# mt2_redraw.net
KiCad netlist of a schematic drawn in EAGLE
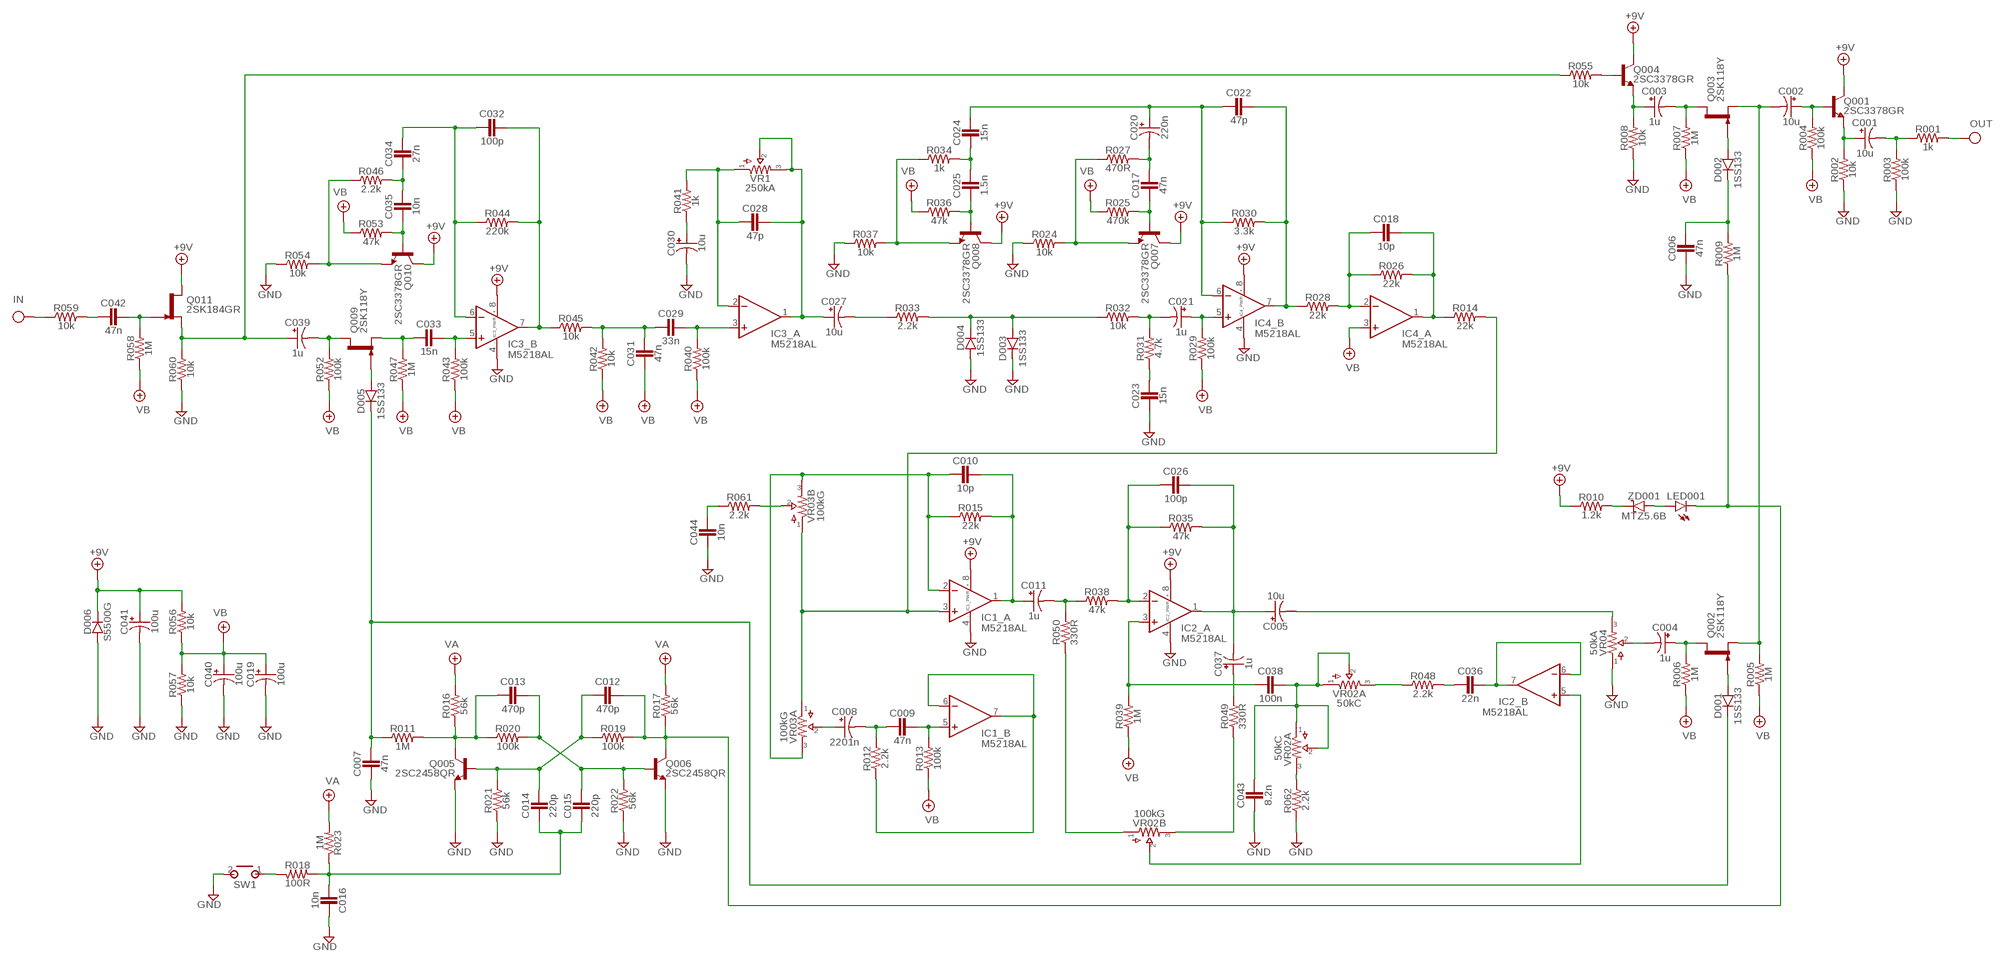
[diagram p0: schematic, sheet 1]

(export (version "E")
  (design (tool "Eeschema 10.0.6"))
  (components
    (comp (ref "C001")
      (value "10u")
      (footprint "eagle-import:050_020")
      (libsource (lib "eagle-import") (part "0500"))
    )
    (comp (ref "C002")
      (value "10u")
      (footprint "eagle-import:050_020")
      (libsource (lib "eagle-import") (part "0500"))
    )
    (comp (ref "C003")
      (value "1u")
      (footprint "eagle-import:050_020")
      (libsource (lib "eagle-import") (part "0500"))
    )
    (comp (ref "C004")
      (value "1u")
      (footprint "eagle-import:050_020")
      (libsource (lib "eagle-import") (part "0500"))
    )
    (comp (ref "C005")
      (value "10u")
      (footprint "eagle-import:050_020")
      (libsource (lib "eagle-import") (part "0500"))
    )
    (comp (ref "C006")
      (value "47n")
      (footprint "eagle-import:BOX_SMALL")
      (libsource (lib "eagle-import") (part "CER/FILMBOX.1"))
    )
    (comp (ref "C007")
      (value "47n")
      (footprint "eagle-import:BOX_SMALL")
      (libsource (lib "eagle-import") (part "CER/FILMBOX.1"))
    )
    (comp (ref "C008")
      (value "2201n")
      (footprint "eagle-import:050_020")
      (libsource (lib "eagle-import") (part "0500"))
    )
    (comp (ref "C009")
      (value "47n")
      (footprint "eagle-import:BOX_SMALL")
      (libsource (lib "eagle-import") (part "CER/FILMBOX.1"))
    )
    (comp (ref "C010")
      (value "10p")
      (footprint "eagle-import:BOX_SMALL")
      (libsource (lib "eagle-import") (part "CER/FILMBOX.1"))
    )
    (comp (ref "C011")
      (value "1u")
      (footprint "eagle-import:050_020")
      (libsource (lib "eagle-import") (part "0500"))
    )
    (comp (ref "C012")
      (value "470p")
      (footprint "eagle-import:BOX_SMALL")
      (libsource (lib "eagle-import") (part "CER/FILMBOX.1"))
    )
    (comp (ref "C013")
      (value "470p")
      (footprint "eagle-import:BOX_SMALL")
      (libsource (lib "eagle-import") (part "CER/FILMBOX.1"))
    )
    (comp (ref "C014")
      (value "220p")
      (footprint "eagle-import:BOX_SMALL")
      (libsource (lib "eagle-import") (part "CER/FILMBOX.1"))
    )
    (comp (ref "C015")
      (value "220p")
      (footprint "eagle-import:BOX_SMALL")
      (libsource (lib "eagle-import") (part "CER/FILMBOX.1"))
    )
    (comp (ref "C016")
      (value "10n")
      (footprint "eagle-import:BOX_SMALL")
      (libsource (lib "eagle-import") (part "CER/FILMBOX.1"))
    )
    (comp (ref "C017")
      (value "47n")
      (footprint "eagle-import:BOX_SMALL")
      (libsource (lib "eagle-import") (part "CER/FILMBOX.1"))
    )
    (comp (ref "C018")
      (value "10p")
      (footprint "eagle-import:BOX_SMALL")
      (libsource (lib "eagle-import") (part "CER/FILMBOX.1"))
    )
    (comp (ref "C019")
      (value "100u")
      (footprint "eagle-import:050_020")
      (libsource (lib "eagle-import") (part "0500"))
    )
    (comp (ref "C020")
      (value "220n")
      (footprint "eagle-import:050_020")
      (libsource (lib "eagle-import") (part "0500"))
    )
    (comp (ref "C021")
      (value "1u")
      (footprint "eagle-import:050_020")
      (libsource (lib "eagle-import") (part "0500"))
    )
    (comp (ref "C022")
      (value "47p")
      (footprint "eagle-import:BOX_SMALL")
      (libsource (lib "eagle-import") (part "CER/FILMBOX.1"))
    )
    (comp (ref "C023")
      (value "15n")
      (footprint "eagle-import:BOX_SMALL")
      (libsource (lib "eagle-import") (part "CER/FILMBOX.1"))
    )
    (comp (ref "C024")
      (value "15n")
      (footprint "eagle-import:BOX_SMALL")
      (libsource (lib "eagle-import") (part "CER/FILMBOX.1"))
    )
    (comp (ref "C025")
      (value "1.5n")
      (footprint "eagle-import:BOX_SMALL")
      (libsource (lib "eagle-import") (part "CER/FILMBOX.1"))
    )
    (comp (ref "C026")
      (value "100p")
      (footprint "eagle-import:BOX_SMALL")
      (libsource (lib "eagle-import") (part "CER/FILMBOX.1"))
    )
    (comp (ref "C027")
      (value "10u")
      (footprint "eagle-import:050_020")
      (libsource (lib "eagle-import") (part "0500"))
    )
    (comp (ref "C028")
      (value "47p")
      (footprint "eagle-import:BOX_SMALL")
      (libsource (lib "eagle-import") (part "CER/FILMBOX.1"))
    )
    (comp (ref "C029")
      (value "33n")
      (footprint "eagle-import:BOX_SMALL")
      (libsource (lib "eagle-import") (part "CER/FILMBOX.1"))
    )
    (comp (ref "C030")
      (value "10u")
      (footprint "eagle-import:050_020")
      (libsource (lib "eagle-import") (part "0500"))
    )
    (comp (ref "C031")
      (value "47n")
      (footprint "eagle-import:BOX_SMALL")
      (libsource (lib "eagle-import") (part "CER/FILMBOX.1"))
    )
    (comp (ref "C032")
      (value "100p")
      (footprint "eagle-import:BOX_SMALL")
      (libsource (lib "eagle-import") (part "CER/FILMBOX.1"))
    )
    (comp (ref "C033")
      (value "15n")
      (footprint "eagle-import:BOX_SMALL")
      (libsource (lib "eagle-import") (part "CER/FILMBOX.1"))
    )
    (comp (ref "C034")
      (value "27n")
      (footprint "eagle-import:BOX_SMALL")
      (libsource (lib "eagle-import") (part "CER/FILMBOX.1"))
    )
    (comp (ref "C035")
      (value "10n")
      (footprint "eagle-import:BOX_SMALL")
      (libsource (lib "eagle-import") (part "CER/FILMBOX.1"))
    )
    (comp (ref "C036")
      (value "22n")
      (footprint "eagle-import:BOX_SMALL")
      (libsource (lib "eagle-import") (part "CER/FILMBOX.1"))
    )
    (comp (ref "C037")
      (value "1u")
      (footprint "eagle-import:050_020")
      (libsource (lib "eagle-import") (part "0500"))
    )
    (comp (ref "C038")
      (value "100n")
      (footprint "eagle-import:BOX_SMALL")
      (libsource (lib "eagle-import") (part "CER/FILMBOX.1"))
    )
    (comp (ref "C039")
      (value "1u")
      (footprint "eagle-import:050_020")
      (libsource (lib "eagle-import") (part "0500"))
    )
    (comp (ref "C040")
      (value "100u")
      (footprint "eagle-import:050_020")
      (libsource (lib "eagle-import") (part "0500"))
    )
    (comp (ref "C041")
      (value "100u")
      (footprint "eagle-import:050_020")
      (libsource (lib "eagle-import") (part "0500"))
    )
    (comp (ref "C042")
      (value "47n")
      (footprint "eagle-import:BOX_SMALL")
      (libsource (lib "eagle-import") (part "CER/FILMBOX.1"))
    )
    (comp (ref "C043")
      (value "8.2n")
      (footprint "eagle-import:BOX_SMALL")
      (libsource (lib "eagle-import") (part "CER/FILMBOX.1"))
    )
    (comp (ref "C044")
      (value "10n")
      (footprint "eagle-import:BOX_SMALL")
      (libsource (lib "eagle-import") (part "CER/FILMBOX.1"))
    )
    (comp (ref "D001")
      (value "1SS133")
      (footprint "eagle-import:DO35-2")
      (libsource (lib "eagle-import") (part "DO35.2"))
    )
    (comp (ref "D002")
      (value "1SS133")
      (footprint "eagle-import:DO35-2")
      (libsource (lib "eagle-import") (part "DO35.2"))
    )
    (comp (ref "D003")
      (value "1SS133")
      (footprint "eagle-import:DO35-2")
      (libsource (lib "eagle-import") (part "DO35.2"))
    )
    (comp (ref "D004")
      (value "1SS133")
      (footprint "eagle-import:DO35-2")
      (libsource (lib "eagle-import") (part "DO35.2"))
    )
    (comp (ref "D005")
      (value "1SS133")
      (footprint "eagle-import:DO35-2")
      (libsource (lib "eagle-import") (part "DO35.2"))
    )
    (comp (ref "D006")
      (value "S5500G")
      (footprint "eagle-import:DO35-2")
      (libsource (lib "eagle-import") (part "DO35.2"))
    )
    (comp (ref "IC1")
      (value "M5218AL")
      (footprint "eagle-import:DIL0")
      (libsource (lib "eagle-import") (part "DUALTH"))
    )
    (comp (ref "IC2")
      (value "M5218AL")
      (footprint "eagle-import:DIL0")
      (libsource (lib "eagle-import") (part "DUALTH"))
    )
    (comp (ref "IC3")
      (value "M5218AL")
      (footprint "eagle-import:DIL0")
      (libsource (lib "eagle-import") (part "DUALTH"))
    )
    (comp (ref "IC4")
      (value "M5218AL")
      (footprint "eagle-import:DIL0")
      (libsource (lib "eagle-import") (part "DUALTH"))
    )
    (comp (ref "LED001")
      (value "LED")
      (footprint "eagle-import:3MM_D")
      (libsource (lib "eagle-import") (part "LED"))
    )
    (comp (ref "Q001")
      (value "2SC3378GR")
      (footprint "eagle-import:TO92-")
      (libsource (lib "eagle-import") (part "2N3904"))
    )
    (comp (ref "Q002")
      (value "2SK118Y")
      (footprint "eagle-import:TO92-")
      (libsource (lib "eagle-import") (part "2N5457"))
    )
    (comp (ref "Q003")
      (value "2SK118Y")
      (footprint "eagle-import:TO92-")
      (libsource (lib "eagle-import") (part "2N5457"))
    )
    (comp (ref "Q004")
      (value "2SC3378GR")
      (footprint "eagle-import:TO92-")
      (libsource (lib "eagle-import") (part "2N3904"))
    )
    (comp (ref "Q005")
      (value "2SC2458QR")
      (footprint "eagle-import:TO92-")
      (libsource (lib "eagle-import") (part "2SC828A"))
    )
    (comp (ref "Q006")
      (value "2SC2458QR")
      (footprint "eagle-import:TO92-")
      (libsource (lib "eagle-import") (part "2SC828A"))
    )
    (comp (ref "Q007")
      (value "2SC3378GR")
      (footprint "eagle-import:TO92-")
      (libsource (lib "eagle-import") (part "2N3904"))
    )
    (comp (ref "Q008")
      (value "2SC3378GR")
      (footprint "eagle-import:TO92-")
      (libsource (lib "eagle-import") (part "2N3904"))
    )
    (comp (ref "Q009")
      (value "2SK118Y")
      (footprint "eagle-import:TO92-")
      (libsource (lib "eagle-import") (part "2N5457"))
    )
    (comp (ref "Q010")
      (value "2SC3378GR")
      (footprint "eagle-import:TO92-")
      (libsource (lib "eagle-import") (part "2N3904"))
    )
    (comp (ref "Q011")
      (value "2SK184GR")
      (footprint "eagle-import:TO92-")
      (libsource (lib "eagle-import") (part "2N5457"))
    )
    (comp (ref "R001")
      (value "1k")
      (footprint "eagle-import:R0207_3")
      (libsource (lib "eagle-import") (part "R_.3B"))
    )
    (comp (ref "R002")
      (value "10k")
      (footprint "eagle-import:R0207_3")
      (libsource (lib "eagle-import") (part "R_.3B"))
    )
    (comp (ref "R003")
      (value "100k")
      (footprint "eagle-import:R0207_3")
      (libsource (lib "eagle-import") (part "R_.3B"))
    )
    (comp (ref "R004")
      (value "100k")
      (footprint "eagle-import:R0207_3")
      (libsource (lib "eagle-import") (part "R_.3B"))
    )
    (comp (ref "R005")
      (value "1M")
      (footprint "eagle-import:R0207_3")
      (libsource (lib "eagle-import") (part "R_.3B"))
    )
    (comp (ref "R006")
      (value "1M")
      (footprint "eagle-import:R0207_3")
      (libsource (lib "eagle-import") (part "R_.3B"))
    )
    (comp (ref "R007")
      (value "1M")
      (footprint "eagle-import:R0207_3")
      (libsource (lib "eagle-import") (part "R_.3B"))
    )
    (comp (ref "R008")
      (value "10k")
      (footprint "eagle-import:R0207_3")
      (libsource (lib "eagle-import") (part "R_.3B"))
    )
    (comp (ref "R009")
      (value "1M")
      (footprint "eagle-import:R0207_3")
      (libsource (lib "eagle-import") (part "R_.3B"))
    )
    (comp (ref "R010")
      (value "1.2k")
      (footprint "eagle-import:R0207_3")
      (libsource (lib "eagle-import") (part "R_.3B"))
    )
    (comp (ref "R011")
      (value "1M")
      (footprint "eagle-import:R0207_3")
      (libsource (lib "eagle-import") (part "R_.3B"))
    )
    (comp (ref "R012")
      (value "2.2k")
      (footprint "eagle-import:R0207_3")
      (libsource (lib "eagle-import") (part "R_.3B"))
    )
    (comp (ref "R013")
      (value "100k")
      (footprint "eagle-import:R0207_3")
      (libsource (lib "eagle-import") (part "R_.3B"))
    )
    (comp (ref "R014")
      (value "22k")
      (footprint "eagle-import:R0207_3")
      (libsource (lib "eagle-import") (part "R_.3B"))
    )
    (comp (ref "R015")
      (value "22k")
      (footprint "eagle-import:R0207_3")
      (libsource (lib "eagle-import") (part "R_.3B"))
    )
    (comp (ref "R016")
      (value "56k")
      (footprint "eagle-import:R0207_3")
      (libsource (lib "eagle-import") (part "R_.3B"))
    )
    (comp (ref "R017")
      (value "56k")
      (footprint "eagle-import:R0207_3")
      (libsource (lib "eagle-import") (part "R_.3B"))
    )
    (comp (ref "R018")
      (value "100R")
      (footprint "eagle-import:R0207_3")
      (libsource (lib "eagle-import") (part "R_.3B"))
    )
    (comp (ref "R019")
      (value "100k")
      (footprint "eagle-import:R0207_3")
      (libsource (lib "eagle-import") (part "R_.3B"))
    )
    (comp (ref "R020")
      (value "100k")
      (footprint "eagle-import:R0207_3")
      (libsource (lib "eagle-import") (part "R_.3B"))
    )
    (comp (ref "R021")
      (value "56k")
      (footprint "eagle-import:R0207_3")
      (libsource (lib "eagle-import") (part "R_.3B"))
    )
    (comp (ref "R022")
      (value "56k")
      (footprint "eagle-import:R0207_3")
      (libsource (lib "eagle-import") (part "R_.3B"))
    )
    (comp (ref "R023")
      (value "1M")
      (footprint "eagle-import:R0207_3")
      (libsource (lib "eagle-import") (part "R_.3B"))
    )
    (comp (ref "R024")
      (value "10k")
      (footprint "eagle-import:R0207_3")
      (libsource (lib "eagle-import") (part "R_.3B"))
    )
    (comp (ref "R025")
      (value "470k")
      (footprint "eagle-import:R0207_3")
      (libsource (lib "eagle-import") (part "R_.3B"))
    )
    (comp (ref "R026")
      (value "22k")
      (footprint "eagle-import:R0207_3")
      (libsource (lib "eagle-import") (part "R_.3B"))
    )
    (comp (ref "R027")
      (value "470R")
      (footprint "eagle-import:R0207_3")
      (libsource (lib "eagle-import") (part "R_.3B"))
    )
    (comp (ref "R028")
      (value "22k")
      (footprint "eagle-import:R0207_3")
      (libsource (lib "eagle-import") (part "R_.3B"))
    )
    (comp (ref "R029")
      (value "100k")
      (footprint "eagle-import:R0207_3")
      (libsource (lib "eagle-import") (part "R_.3B"))
    )
    (comp (ref "R030")
      (value "3.3k")
      (footprint "eagle-import:R0207_3")
      (libsource (lib "eagle-import") (part "R_.3B"))
    )
    (comp (ref "R031")
      (value "4.7k")
      (footprint "eagle-import:R0207_3")
      (libsource (lib "eagle-import") (part "R_.3B"))
    )
    (comp (ref "R032")
      (value "10k")
      (footprint "eagle-import:R0207_3")
      (libsource (lib "eagle-import") (part "R_.3B"))
    )
    (comp (ref "R033")
      (value "2.2k")
      (footprint "eagle-import:R0207_3")
      (libsource (lib "eagle-import") (part "R_.3B"))
    )
    (comp (ref "R034")
      (value "1k")
      (footprint "eagle-import:R0207_3")
      (libsource (lib "eagle-import") (part "R_.3B"))
    )
    (comp (ref "R035")
      (value "47k")
      (footprint "eagle-import:R0207_3")
      (libsource (lib "eagle-import") (part "R_.3B"))
    )
    (comp (ref "R036")
      (value "47k")
      (footprint "eagle-import:R0207_3")
      (libsource (lib "eagle-import") (part "R_.3B"))
    )
    (comp (ref "R037")
      (value "10k")
      (footprint "eagle-import:R0207_3")
      (libsource (lib "eagle-import") (part "R_.3B"))
    )
    (comp (ref "R038")
      (value "47k")
      (footprint "eagle-import:R0207_3")
      (libsource (lib "eagle-import") (part "R_.3B"))
    )
    (comp (ref "R039")
      (value "1M")
      (footprint "eagle-import:R0207_3")
      (libsource (lib "eagle-import") (part "R_.3B"))
    )
    (comp (ref "R040")
      (value "100k")
      (footprint "eagle-import:R0207_3")
      (libsource (lib "eagle-import") (part "R_.3B"))
    )
    (comp (ref "R041")
      (value "1k")
      (footprint "eagle-import:R0207_3")
      (libsource (lib "eagle-import") (part "R_.3B"))
    )
    (comp (ref "R042")
      (value "10k")
      (footprint "eagle-import:R0207_3")
      (libsource (lib "eagle-import") (part "R_.3B"))
    )
    (comp (ref "R043")
      (value "100k")
      (footprint "eagle-import:R0207_3")
      (libsource (lib "eagle-import") (part "R_.3B"))
    )
    (comp (ref "R044")
      (value "220k")
      (footprint "eagle-import:R0207_3")
      (libsource (lib "eagle-import") (part "R_.3B"))
    )
    (comp (ref "R045")
      (value "10k")
      (footprint "eagle-import:R0207_3")
      (libsource (lib "eagle-import") (part "R_.3B"))
    )
    (comp (ref "R046")
      (value "2.2k")
      (footprint "eagle-import:R0207_3")
      (libsource (lib "eagle-import") (part "R_.3B"))
    )
    (comp (ref "R047")
      (value "1M")
      (footprint "eagle-import:R0207_3")
      (libsource (lib "eagle-import") (part "R_.3B"))
    )
    (comp (ref "R048")
      (value "2.2k")
      (footprint "eagle-import:R0207_3")
      (libsource (lib "eagle-import") (part "R_.3B"))
    )
    (comp (ref "R049")
      (value "330R")
      (footprint "eagle-import:R0207_3")
      (libsource (lib "eagle-import") (part "R_.3B"))
    )
    (comp (ref "R050")
      (value "330R")
      (footprint "eagle-import:R0207_3")
      (libsource (lib "eagle-import") (part "R_.3B"))
    )
    (comp (ref "R052")
      (value "100k")
      (footprint "eagle-import:R0207_3")
      (libsource (lib "eagle-import") (part "R_.3B"))
    )
    (comp (ref "R053")
      (value "47k")
      (footprint "eagle-import:R0207_3")
      (libsource (lib "eagle-import") (part "R_.3B"))
    )
    (comp (ref "R054")
      (value "10k")
      (footprint "eagle-import:R0207_3")
      (libsource (lib "eagle-import") (part "R_.3B"))
    )
    (comp (ref "R055")
      (value "10k")
      (footprint "eagle-import:R0207_3")
      (libsource (lib "eagle-import") (part "R_.3B"))
    )
    (comp (ref "R056")
      (value "10k")
      (footprint "eagle-import:R0207_3")
      (libsource (lib "eagle-import") (part "R_.3B"))
    )
    (comp (ref "R057")
      (value "10k")
      (footprint "eagle-import:R0207_3")
      (libsource (lib "eagle-import") (part "R_.3B"))
    )
    (comp (ref "R058")
      (value "1M")
      (footprint "eagle-import:R0207_3")
      (libsource (lib "eagle-import") (part "R_.3B"))
    )
    (comp (ref "R059")
      (value "10k")
      (footprint "eagle-import:R0207_3")
      (libsource (lib "eagle-import") (part "R_.3B"))
    )
    (comp (ref "R060")
      (value "10k")
      (footprint "eagle-import:R0207_3")
      (libsource (lib "eagle-import") (part "R_.3B"))
    )
    (comp (ref "R061")
      (value "2.2k")
      (footprint "eagle-import:R0207_3")
      (libsource (lib "eagle-import") (part "R_.3B"))
    )
    (comp (ref "R062")
      (value "2.2k")
      (footprint "eagle-import:R0207_3")
      (libsource (lib "eagle-import") (part "R_.3B"))
    )
    (comp (ref "SW1")
      (value "MOMENTARY")
      (footprint "eagle-import:SPST")
      (libsource (lib "eagle-import") (part "MOMENTARY"))
    )
    (comp (ref "VR1")
      (value "250kA")
      (footprint "eagle-import:16MM")
      (libsource (lib "eagle-import") (part "POTS16MM"))
    )
    (comp (ref "VR02A")
      (value "50kC")
      (footprint "eagle-import:16MM")
      (libsource (lib "eagle-import") (part "POTS16MM"))
    )
    (comp (ref "VR02A ")
      (value "50kC")
      (footprint "eagle-import:16MM")
      (libsource (lib "eagle-import") (part "POTS16MM"))
    )
    (comp (ref "VR02B")
      (value "100kG")
      (footprint "eagle-import:16MM")
      (libsource (lib "eagle-import") (part "POTS16MM"))
    )
    (comp (ref "VR03A")
      (value "100kG")
      (footprint "eagle-import:16MM")
      (libsource (lib "eagle-import") (part "POTS16MM"))
    )
    (comp (ref "VR03B")
      (value "100kG")
      (footprint "eagle-import:16MM")
      (libsource (lib "eagle-import") (part "POTS16MM"))
    )
    (comp (ref "VR04")
      (value "50kA")
      (footprint "eagle-import:16MM")
      (libsource (lib "eagle-import") (part "POTS16MM"))
    )
    (comp (ref "ZD001")
      (value "MTZ5.6B")
      (footprint "eagle-import:DO41-2")
      (libsource (lib "eagle-import") (part "ZENER.2"))
    )
  )
  (nets
    (net (code "1") (name "+9V") (class "Default")
      (node (ref "C041") (pin "+") (pinfunction "+_+") (pintype "passive"))
      (node (ref "D006") (pin "C") (pinfunction "C_C") (pintype "passive"))
      (node (ref "IC1") (pin "8") (pinfunction "V+_8") (pintype "power_in"))
      (node (ref "IC2") (pin "8") (pinfunction "V+_8") (pintype "power_in"))
      (node (ref "IC3") (pin "8") (pinfunction "V+_8") (pintype "power_in"))
      (node (ref "IC4") (pin "8") (pinfunction "V+_8") (pintype "power_in"))
      (node (ref "Q001") (pin "1") (pinfunction "C_1") (pintype "passive"))
      (node (ref "Q004") (pin "1") (pinfunction "C_1") (pintype "passive"))
      (node (ref "Q007") (pin "1") (pinfunction "C_1") (pintype "passive"))
      (node (ref "Q008") (pin "1") (pinfunction "C_1") (pintype "passive"))
      (node (ref "Q010") (pin "1") (pinfunction "C_1") (pintype "passive"))
      (node (ref "Q011") (pin "3") (pinfunction "D_3") (pintype "passive"))
      (node (ref "R010") (pin "1") (pinfunction "1_1") (pintype "passive"))
      (node (ref "R056") (pin "2") (pinfunction "2_2") (pintype "passive"))
    )
    (net (code "2") (name "GND") (class "Default")
      (node (ref "C006") (pin "2") (pinfunction "2_2") (pintype "passive"))
      (node (ref "C007") (pin "2") (pinfunction "2_2") (pintype "passive"))
      (node (ref "C016") (pin "2") (pinfunction "2_2") (pintype "passive"))
      (node (ref "C019") (pin "-") (pinfunction "-_-") (pintype "passive"))
      (node (ref "C023") (pin "2") (pinfunction "2_2") (pintype "passive"))
      (node (ref "C030") (pin "-") (pinfunction "-_-") (pintype "passive"))
      (node (ref "C040") (pin "-") (pinfunction "-_-") (pintype "passive"))
      (node (ref "C041") (pin "-") (pinfunction "-_-") (pintype "passive"))
      (node (ref "C043") (pin "2") (pinfunction "2_2") (pintype "passive"))
      (node (ref "C044") (pin "2") (pinfunction "2_2") (pintype "passive"))
      (node (ref "D003") (pin "C") (pinfunction "C_C") (pintype "passive"))
      (node (ref "D004") (pin "A") (pinfunction "A_A") (pintype "passive"))
      (node (ref "D006") (pin "A") (pinfunction "A_A") (pintype "passive"))
      (node (ref "IC1") (pin "4") (pinfunction "V-_4") (pintype "power_in"))
      (node (ref "IC2") (pin "4") (pinfunction "V-_4") (pintype "power_in"))
      (node (ref "IC3") (pin "4") (pinfunction "V-_4") (pintype "power_in"))
      (node (ref "IC4") (pin "4") (pinfunction "V-_4") (pintype "power_in"))
      (node (ref "Q005") (pin "3") (pinfunction "E_3") (pintype "passive"))
      (node (ref "Q006") (pin "3") (pinfunction "E_3") (pintype "passive"))
      (node (ref "R002") (pin "1") (pinfunction "1_1") (pintype "passive"))
      (node (ref "R003") (pin "1") (pinfunction "1_1") (pintype "passive"))
      (node (ref "R008") (pin "1") (pinfunction "1_1") (pintype "passive"))
      (node (ref "R021") (pin "1") (pinfunction "1_1") (pintype "passive"))
      (node (ref "R022") (pin "1") (pinfunction "1_1") (pintype "passive"))
      (node (ref "R024") (pin "1") (pinfunction "1_1") (pintype "passive"))
      (node (ref "R037") (pin "1") (pinfunction "1_1") (pintype "passive"))
      (node (ref "R054") (pin "1") (pinfunction "1_1") (pintype "passive"))
      (node (ref "R057") (pin "1") (pinfunction "1_1") (pintype "passive"))
      (node (ref "R060") (pin "1") (pinfunction "1_1") (pintype "passive"))
      (node (ref "R062") (pin "1") (pinfunction "1_1") (pintype "passive"))
      (node (ref "SW1") (pin "2") (pinfunction "S_2") (pintype "passive"))
      (node (ref "VR04") (pin "1") (pinfunction "1_1") (pintype "passive"))
    )
    (net (code "3") (name "IN") (class "Default")
      (node (ref "R059") (pin "1") (pinfunction "1_1") (pintype "passive"))
    )
    (net (code "4") (name "Net-(C001-Pad-)") (class "Default")
      (node (ref "C001") (pin "-") (pinfunction "-_-") (pintype "passive"))
      (node (ref "R001") (pin "1") (pinfunction "1_1") (pintype "passive"))
      (node (ref "R003") (pin "2") (pinfunction "2_2") (pintype "passive"))
    )
    (net (code "5") (name "Net-(C004-Pad-)") (class "Default")
      (node (ref "C004") (pin "-") (pinfunction "-_-") (pintype "passive"))
      (node (ref "VR04") (pin "2") (pinfunction "2_2") (pintype "passive"))
    )
    (net (code "6") (name "Net-(C005-Pad-)") (class "Default")
      (node (ref "C005") (pin "-") (pinfunction "-_-") (pintype "passive"))
      (node (ref "VR04") (pin "3") (pinfunction "3_3") (pintype "passive"))
    )
    (net (code "7") (name "Net-(C006-Pad1)") (class "Default")
      (node (ref "C006") (pin "1") (pinfunction "1_1") (pintype "passive"))
      (node (ref "D002") (pin "C") (pinfunction "C_C") (pintype "passive"))
      (node (ref "R009") (pin "2") (pinfunction "2_2") (pintype "passive"))
    )
    (net (code "8") (name "Net-(C007-Pad1)") (class "Default")
      (node (ref "C007") (pin "1") (pinfunction "1_1") (pintype "passive"))
      (node (ref "D001") (pin "C") (pinfunction "C_C") (pintype "passive"))
      (node (ref "D005") (pin "C") (pinfunction "C_C") (pintype "passive"))
      (node (ref "R011") (pin "1") (pinfunction "1_1") (pintype "passive"))
    )
    (net (code "9") (name "Net-(C008-Pad+)") (class "Default")
      (node (ref "C008") (pin "+") (pinfunction "+_+") (pintype "passive"))
      (node (ref "VR03A") (pin "2") (pinfunction "2_2") (pintype "passive"))
    )
    (net (code "10") (name "Net-(C008-Pad-)") (class "Default")
      (node (ref "C008") (pin "-") (pinfunction "-_-") (pintype "passive"))
      (node (ref "C009") (pin "2") (pinfunction "2_2") (pintype "passive"))
      (node (ref "R012") (pin "2") (pinfunction "2_2") (pintype "passive"))
    )
    (net (code "11") (name "Net-(C011-Pad-)") (class "Default")
      (node (ref "C011") (pin "-") (pinfunction "-_-") (pintype "passive"))
      (node (ref "R038") (pin "1") (pinfunction "1_1") (pintype "passive"))
      (node (ref "R050") (pin "2") (pinfunction "2_2") (pintype "passive"))
    )
    (net (code "12") (name "Net-(C014-Pad2)") (class "Default")
      (node (ref "C014") (pin "2") (pinfunction "2_2") (pintype "passive"))
      (node (ref "C015") (pin "2") (pinfunction "2_2") (pintype "passive"))
      (node (ref "C016") (pin "1") (pinfunction "1_1") (pintype "passive"))
      (node (ref "R018") (pin "1") (pinfunction "1_1") (pintype "passive"))
      (node (ref "R023") (pin "1") (pinfunction "1_1") (pintype "passive"))
    )
    (net (code "13") (name "Net-(C017-Pad1)") (class "Default")
      (node (ref "C017") (pin "1") (pinfunction "1_1") (pintype "passive"))
      (node (ref "C020") (pin "-") (pinfunction "-_-") (pintype "passive"))
      (node (ref "R027") (pin "2") (pinfunction "2_2") (pintype "passive"))
    )
    (net (code "14") (name "Net-(C021-Pad-)") (class "Default")
      (node (ref "C021") (pin "-") (pinfunction "-_-") (pintype "passive"))
      (node (ref "R031") (pin "2") (pinfunction "2_2") (pintype "passive"))
      (node (ref "R032") (pin "2") (pinfunction "2_2") (pintype "passive"))
    )
    (net (code "15") (name "Net-(C023-Pad1)") (class "Default")
      (node (ref "C023") (pin "1") (pinfunction "1_1") (pintype "passive"))
      (node (ref "R031") (pin "1") (pinfunction "1_1") (pintype "passive"))
    )
    (net (code "16") (name "Net-(C024-Pad2)") (class "Default")
      (node (ref "C024") (pin "2") (pinfunction "2_2") (pintype "passive"))
      (node (ref "C025") (pin "1") (pinfunction "1_1") (pintype "passive"))
      (node (ref "R034") (pin "2") (pinfunction "2_2") (pintype "passive"))
    )
    (net (code "17") (name "Net-(C027-Pad-)") (class "Default")
      (node (ref "C027") (pin "-") (pinfunction "-_-") (pintype "passive"))
      (node (ref "R033") (pin "1") (pinfunction "1_1") (pintype "passive"))
    )
    (net (code "18") (name "Net-(C029-Pad2)") (class "Default")
      (node (ref "C029") (pin "2") (pinfunction "2_2") (pintype "passive"))
      (node (ref "C031") (pin "1") (pinfunction "1_1") (pintype "passive"))
      (node (ref "R042") (pin "2") (pinfunction "2_2") (pintype "passive"))
      (node (ref "R045") (pin "2") (pinfunction "2_2") (pintype "passive"))
    )
    (net (code "19") (name "Net-(C030-Pad+)") (class "Default")
      (node (ref "C030") (pin "+") (pinfunction "+_+") (pintype "passive"))
      (node (ref "R041") (pin "1") (pinfunction "1_1") (pintype "passive"))
    )
    (net (code "20") (name "Net-(C034-Pad2)") (class "Default")
      (node (ref "C034") (pin "2") (pinfunction "2_2") (pintype "passive"))
      (node (ref "C035") (pin "1") (pinfunction "1_1") (pintype "passive"))
      (node (ref "R046") (pin "2") (pinfunction "2_2") (pintype "passive"))
    )
    (net (code "21") (name "Net-(C036-Pad2)") (class "Default")
      (node (ref "C036") (pin "2") (pinfunction "2_2") (pintype "passive"))
      (node (ref "R048") (pin "2") (pinfunction "2_2") (pintype "passive"))
    )
    (net (code "22") (name "Net-(C037-Pad+)") (class "Default")
      (node (ref "C037") (pin "+") (pinfunction "+_+") (pintype "passive"))
      (node (ref "R049") (pin "2") (pinfunction "2_2") (pintype "passive"))
    )
    (net (code "23") (name "Net-(C038-Pad1)") (class "Default")
      (node (ref "C038") (pin "1") (pinfunction "1_1") (pintype "passive"))
      (node (ref "C043") (pin "1") (pinfunction "1_1") (pintype "passive"))
      (node (ref "VR02A") (pin "1") (pinfunction "1_1") (pintype "passive"))
      (node (ref "VR02A") (pin "2") (pinfunction "2_2") (pintype "passive"))
      (node (ref "VR02A ") (pin "1") (pinfunction "1_1") (pintype "passive"))
      (node (ref "VR02A ") (pin "2") (pinfunction "2_2") (pintype "passive"))
    )
    (net (code "24") (name "Net-(C042-Pad2)") (class "Default")
      (node (ref "C042") (pin "2") (pinfunction "2_2") (pintype "passive"))
      (node (ref "R059") (pin "2") (pinfunction "2_2") (pintype "passive"))
    )
    (net (code "25") (name "Net-(C044-Pad1)") (class "Default")
      (node (ref "C044") (pin "1") (pinfunction "1_1") (pintype "passive"))
      (node (ref "R061") (pin "1") (pinfunction "1_1") (pintype "passive"))
    )
    (net (code "26") (name "Net-(D003-PadA)") (class "Default")
      (node (ref "D003") (pin "A") (pinfunction "A_A") (pintype "passive"))
      (node (ref "D004") (pin "C") (pinfunction "C_C") (pintype "passive"))
      (node (ref "R032") (pin "1") (pinfunction "1_1") (pintype "passive"))
      (node (ref "R033") (pin "2") (pinfunction "2_2") (pintype "passive"))
    )
    (net (code "27") (name "Net-(IC1A-+IN)") (class "Default")
      (node (ref "IC1") (pin "3") (pinfunction "+IN_3") (pintype "input"))
      (node (ref "R014") (pin "2") (pinfunction "2_2") (pintype "passive"))
      (node (ref "VR03A") (pin "1") (pinfunction "1_1") (pintype "passive"))
      (node (ref "VR03B") (pin "1") (pinfunction "1_1") (pintype "passive"))
    )
    (net (code "28") (name "Net-(IC1A--IN)") (class "Default")
      (node (ref "C010") (pin "2") (pinfunction "2_2") (pintype "passive"))
      (node (ref "IC1") (pin "2") (pinfunction "-IN_2") (pintype "input"))
      (node (ref "R015") (pin "1") (pinfunction "1_1") (pintype "passive"))
      (node (ref "VR03A") (pin "3") (pinfunction "3_3") (pintype "passive"))
      (node (ref "VR03B") (pin "3") (pinfunction "3_3") (pintype "passive"))
    )
    (net (code "29") (name "Net-(IC1A-OUT)") (class "Default")
      (node (ref "C010") (pin "1") (pinfunction "1_1") (pintype "passive"))
      (node (ref "C011") (pin "+") (pinfunction "+_+") (pintype "passive"))
      (node (ref "IC1") (pin "1") (pinfunction "OUT_1") (pintype "output"))
      (node (ref "R015") (pin "2") (pinfunction "2_2") (pintype "passive"))
    )
    (net (code "30") (name "Net-(IC1B-+IN)") (class "Default")
      (node (ref "C009") (pin "1") (pinfunction "1_1") (pintype "passive"))
      (node (ref "IC1") (pin "5") (pinfunction "+IN_5") (pintype "input"))
      (node (ref "R013") (pin "2") (pinfunction "2_2") (pintype "passive"))
    )
    (net (code "31") (name "Net-(IC1B--IN)") (class "Default")
      (node (ref "IC1") (pin "6") (pinfunction "-IN_6") (pintype "input"))
      (node (ref "IC1") (pin "7") (pinfunction "OUT_7") (pintype "output"))
      (node (ref "R012") (pin "1") (pinfunction "1_1") (pintype "passive"))
    )
    (net (code "32") (name "Net-(IC2A-+IN)") (class "Default")
      (node (ref "C038") (pin "2") (pinfunction "2_2") (pintype "passive"))
      (node (ref "IC2") (pin "3") (pinfunction "+IN_3") (pintype "input"))
      (node (ref "R039") (pin "2") (pinfunction "2_2") (pintype "passive"))
    )
    (net (code "33") (name "Net-(IC2A--IN)") (class "Default")
      (node (ref "C026") (pin "2") (pinfunction "2_2") (pintype "passive"))
      (node (ref "IC2") (pin "2") (pinfunction "-IN_2") (pintype "input"))
      (node (ref "R035") (pin "1") (pinfunction "1_1") (pintype "passive"))
      (node (ref "R038") (pin "2") (pinfunction "2_2") (pintype "passive"))
    )
    (net (code "34") (name "Net-(IC2A-OUT)") (class "Default")
      (node (ref "C005") (pin "+") (pinfunction "+_+") (pintype "passive"))
      (node (ref "C026") (pin "1") (pinfunction "1_1") (pintype "passive"))
      (node (ref "C037") (pin "-") (pinfunction "-_-") (pintype "passive"))
      (node (ref "IC2") (pin "1") (pinfunction "OUT_1") (pintype "output"))
      (node (ref "R035") (pin "2") (pinfunction "2_2") (pintype "passive"))
    )
    (net (code "35") (name "Net-(IC2B-+IN)") (class "Default")
      (node (ref "IC2") (pin "5") (pinfunction "+IN_5") (pintype "input"))
      (node (ref "VR02B") (pin "2") (pinfunction "2_2") (pintype "passive"))
    )
    (net (code "36") (name "Net-(IC2B--IN)") (class "Default")
      (node (ref "C036") (pin "1") (pinfunction "1_1") (pintype "passive"))
      (node (ref "IC2") (pin "6") (pinfunction "-IN_6") (pintype "input"))
      (node (ref "IC2") (pin "7") (pinfunction "OUT_7") (pintype "output"))
    )
    (net (code "37") (name "Net-(IC3A-+IN)") (class "Default")
      (node (ref "C029") (pin "1") (pinfunction "1_1") (pintype "passive"))
      (node (ref "IC3") (pin "3") (pinfunction "+IN_3") (pintype "input"))
      (node (ref "R040") (pin "2") (pinfunction "2_2") (pintype "passive"))
    )
    (net (code "38") (name "Net-(IC3A--IN)") (class "Default")
      (node (ref "C028") (pin "2") (pinfunction "2_2") (pintype "passive"))
      (node (ref "IC3") (pin "2") (pinfunction "-IN_2") (pintype "input"))
      (node (ref "R041") (pin "2") (pinfunction "2_2") (pintype "passive"))
      (node (ref "VR1") (pin "1") (pinfunction "1_1") (pintype "passive"))
    )
    (net (code "39") (name "Net-(IC3A-OUT)") (class "Default")
      (node (ref "C027") (pin "+") (pinfunction "+_+") (pintype "passive"))
      (node (ref "C028") (pin "1") (pinfunction "1_1") (pintype "passive"))
      (node (ref "IC3") (pin "1") (pinfunction "OUT_1") (pintype "output"))
      (node (ref "VR1") (pin "2") (pinfunction "2_2") (pintype "passive"))
      (node (ref "VR1") (pin "3") (pinfunction "3_3") (pintype "passive"))
    )
    (net (code "40") (name "Net-(IC3B-+IN)") (class "Default")
      (node (ref "C033") (pin "1") (pinfunction "1_1") (pintype "passive"))
      (node (ref "IC3") (pin "5") (pinfunction "+IN_5") (pintype "input"))
      (node (ref "R043") (pin "2") (pinfunction "2_2") (pintype "passive"))
    )
    (net (code "41") (name "Net-(IC3B--IN)") (class "Default")
      (node (ref "C032") (pin "2") (pinfunction "2_2") (pintype "passive"))
      (node (ref "C034") (pin "1") (pinfunction "1_1") (pintype "passive"))
      (node (ref "IC3") (pin "6") (pinfunction "-IN_6") (pintype "input"))
      (node (ref "R044") (pin "1") (pinfunction "1_1") (pintype "passive"))
    )
    (net (code "42") (name "Net-(IC3B-OUT)") (class "Default")
      (node (ref "C032") (pin "1") (pinfunction "1_1") (pintype "passive"))
      (node (ref "IC3") (pin "7") (pinfunction "OUT_7") (pintype "output"))
      (node (ref "R044") (pin "2") (pinfunction "2_2") (pintype "passive"))
      (node (ref "R045") (pin "1") (pinfunction "1_1") (pintype "passive"))
    )
    (net (code "43") (name "Net-(IC4A--IN)") (class "Default")
      (node (ref "C018") (pin "2") (pinfunction "2_2") (pintype "passive"))
      (node (ref "IC4") (pin "2") (pinfunction "-IN_2") (pintype "input"))
      (node (ref "R026") (pin "1") (pinfunction "1_1") (pintype "passive"))
      (node (ref "R028") (pin "2") (pinfunction "2_2") (pintype "passive"))
    )
    (net (code "44") (name "Net-(IC4A-OUT)") (class "Default")
      (node (ref "C018") (pin "1") (pinfunction "1_1") (pintype "passive"))
      (node (ref "IC4") (pin "1") (pinfunction "OUT_1") (pintype "output"))
      (node (ref "R014") (pin "1") (pinfunction "1_1") (pintype "passive"))
      (node (ref "R026") (pin "2") (pinfunction "2_2") (pintype "passive"))
    )
    (net (code "45") (name "Net-(IC4B-+IN)") (class "Default")
      (node (ref "C021") (pin "+") (pinfunction "+_+") (pintype "passive"))
      (node (ref "IC4") (pin "5") (pinfunction "+IN_5") (pintype "input"))
      (node (ref "R029") (pin "2") (pinfunction "2_2") (pintype "passive"))
    )
    (net (code "46") (name "Net-(IC4B--IN)") (class "Default")
      (node (ref "C020") (pin "+") (pinfunction "+_+") (pintype "passive"))
      (node (ref "C022") (pin "2") (pinfunction "2_2") (pintype "passive"))
      (node (ref "C024") (pin "1") (pinfunction "1_1") (pintype "passive"))
      (node (ref "IC4") (pin "6") (pinfunction "-IN_6") (pintype "input"))
      (node (ref "R030") (pin "1") (pinfunction "1_1") (pintype "passive"))
    )
    (net (code "47") (name "Net-(IC4B-OUT)") (class "Default")
      (node (ref "C022") (pin "1") (pinfunction "1_1") (pintype "passive"))
      (node (ref "IC4") (pin "7") (pinfunction "OUT_7") (pintype "output"))
      (node (ref "R028") (pin "1") (pinfunction "1_1") (pintype "passive"))
      (node (ref "R030") (pin "2") (pinfunction "2_2") (pintype "passive"))
    )
    (net (code "48") (name "Net-(LED001-A)") (class "Default")
      (node (ref "LED001") (pin "ANODE") (pinfunction "A_ANODE") (pintype "passive"))
      (node (ref "ZD001") (pin "A") (pinfunction "A_A") (pintype "passive"))
    )
    (net (code "49") (name "Net-(LED001-C)") (class "Default")
      (node (ref "C012") (pin "1") (pinfunction "1_1") (pintype "passive"))
      (node (ref "LED001") (pin "P$1") (pinfunction "C_P$1") (pintype "passive"))
      (node (ref "Q006") (pin "2") (pinfunction "C_2") (pintype "passive"))
      (node (ref "R009") (pin "1") (pinfunction "1_1") (pintype "passive"))
      (node (ref "R017") (pin "1") (pinfunction "1_1") (pintype "passive"))
      (node (ref "R019") (pin "2") (pinfunction "2_2") (pintype "passive"))
    )
    (net (code "50") (name "Net-(Q001-B)") (class "Default")
      (node (ref "C002") (pin "+") (pinfunction "+_+") (pintype "passive"))
      (node (ref "Q001") (pin "2") (pinfunction "B_2") (pintype "passive"))
      (node (ref "R004") (pin "2") (pinfunction "2_2") (pintype "passive"))
    )
    (net (code "51") (name "Net-(Q001-E)") (class "Default")
      (node (ref "C001") (pin "+") (pinfunction "+_+") (pintype "passive"))
      (node (ref "Q001") (pin "3") (pinfunction "E_3") (pintype "passive"))
      (node (ref "R002") (pin "2") (pinfunction "2_2") (pintype "passive"))
    )
    (net (code "52") (name "Net-(Q002-D)") (class "Default")
      (node (ref "C004") (pin "+") (pinfunction "+_+") (pintype "passive"))
      (node (ref "Q002") (pin "3") (pinfunction "D_3") (pintype "passive"))
      (node (ref "R006") (pin "2") (pinfunction "2_2") (pintype "passive"))
    )
    (net (code "53") (name "Net-(Q002-G)") (class "Default")
      (node (ref "D001") (pin "A") (pinfunction "A_A") (pintype "passive"))
      (node (ref "Q002") (pin "1") (pinfunction "G_1") (pintype "passive"))
    )
    (net (code "54") (name "Net-(Q002-S)") (class "Default")
      (node (ref "C002") (pin "-") (pinfunction "-_-") (pintype "passive"))
      (node (ref "Q002") (pin "2") (pinfunction "S_2") (pintype "passive"))
      (node (ref "Q003") (pin "2") (pinfunction "S_2") (pintype "passive"))
      (node (ref "R005") (pin "2") (pinfunction "2_2") (pintype "passive"))
    )
    (net (code "55") (name "Net-(Q003-D)") (class "Default")
      (node (ref "C003") (pin "-") (pinfunction "-_-") (pintype "passive"))
      (node (ref "Q003") (pin "3") (pinfunction "D_3") (pintype "passive"))
      (node (ref "R007") (pin "2") (pinfunction "2_2") (pintype "passive"))
    )
    (net (code "56") (name "Net-(Q003-G)") (class "Default")
      (node (ref "D002") (pin "A") (pinfunction "A_A") (pintype "passive"))
      (node (ref "Q003") (pin "1") (pinfunction "G_1") (pintype "passive"))
    )
    (net (code "57") (name "Net-(Q004-B)") (class "Default")
      (node (ref "Q004") (pin "2") (pinfunction "B_2") (pintype "passive"))
      (node (ref "R055") (pin "2") (pinfunction "2_2") (pintype "passive"))
    )
    (net (code "58") (name "Net-(Q004-E)") (class "Default")
      (node (ref "C003") (pin "+") (pinfunction "+_+") (pintype "passive"))
      (node (ref "Q004") (pin "3") (pinfunction "E_3") (pintype "passive"))
      (node (ref "R008") (pin "2") (pinfunction "2_2") (pintype "passive"))
    )
    (net (code "59") (name "Net-(Q005-B)") (class "Default")
      (node (ref "C012") (pin "2") (pinfunction "2_2") (pintype "passive"))
      (node (ref "C014") (pin "1") (pinfunction "1_1") (pintype "passive"))
      (node (ref "Q005") (pin "1") (pinfunction "B_1") (pintype "passive"))
      (node (ref "R019") (pin "1") (pinfunction "1_1") (pintype "passive"))
      (node (ref "R021") (pin "2") (pinfunction "2_2") (pintype "passive"))
    )
    (net (code "60") (name "Net-(Q005-C)") (class "Default")
      (node (ref "C013") (pin "2") (pinfunction "2_2") (pintype "passive"))
      (node (ref "Q005") (pin "2") (pinfunction "C_2") (pintype "passive"))
      (node (ref "R011") (pin "2") (pinfunction "2_2") (pintype "passive"))
      (node (ref "R016") (pin "1") (pinfunction "1_1") (pintype "passive"))
      (node (ref "R020") (pin "1") (pinfunction "1_1") (pintype "passive"))
    )
    (net (code "61") (name "Net-(Q006-B)") (class "Default")
      (node (ref "C013") (pin "1") (pinfunction "1_1") (pintype "passive"))
      (node (ref "C015") (pin "1") (pinfunction "1_1") (pintype "passive"))
      (node (ref "Q006") (pin "1") (pinfunction "B_1") (pintype "passive"))
      (node (ref "R020") (pin "2") (pinfunction "2_2") (pintype "passive"))
      (node (ref "R022") (pin "2") (pinfunction "2_2") (pintype "passive"))
    )
    (net (code "62") (name "Net-(Q007-B)") (class "Default")
      (node (ref "C017") (pin "2") (pinfunction "2_2") (pintype "passive"))
      (node (ref "Q007") (pin "2") (pinfunction "B_2") (pintype "passive"))
      (node (ref "R025") (pin "2") (pinfunction "2_2") (pintype "passive"))
    )
    (net (code "63") (name "Net-(Q007-E)") (class "Default")
      (node (ref "Q007") (pin "3") (pinfunction "E_3") (pintype "passive"))
      (node (ref "R024") (pin "2") (pinfunction "2_2") (pintype "passive"))
      (node (ref "R027") (pin "1") (pinfunction "1_1") (pintype "passive"))
    )
    (net (code "64") (name "Net-(Q008-B)") (class "Default")
      (node (ref "C025") (pin "2") (pinfunction "2_2") (pintype "passive"))
      (node (ref "Q008") (pin "2") (pinfunction "B_2") (pintype "passive"))
      (node (ref "R036") (pin "2") (pinfunction "2_2") (pintype "passive"))
    )
    (net (code "65") (name "Net-(Q008-E)") (class "Default")
      (node (ref "Q008") (pin "3") (pinfunction "E_3") (pintype "passive"))
      (node (ref "R034") (pin "1") (pinfunction "1_1") (pintype "passive"))
      (node (ref "R037") (pin "2") (pinfunction "2_2") (pintype "passive"))
    )
    (net (code "66") (name "Net-(Q009-D)") (class "Default")
      (node (ref "C039") (pin "-") (pinfunction "-_-") (pintype "passive"))
      (node (ref "Q009") (pin "3") (pinfunction "D_3") (pintype "passive"))
      (node (ref "R052") (pin "2") (pinfunction "2_2") (pintype "passive"))
    )
    (net (code "67") (name "Net-(Q009-G)") (class "Default")
      (node (ref "D005") (pin "A") (pinfunction "A_A") (pintype "passive"))
      (node (ref "Q009") (pin "1") (pinfunction "G_1") (pintype "passive"))
    )
    (net (code "68") (name "Net-(Q009-S)") (class "Default")
      (node (ref "C033") (pin "2") (pinfunction "2_2") (pintype "passive"))
      (node (ref "Q009") (pin "2") (pinfunction "S_2") (pintype "passive"))
      (node (ref "R047") (pin "2") (pinfunction "2_2") (pintype "passive"))
    )
    (net (code "69") (name "Net-(Q010-B)") (class "Default")
      (node (ref "C035") (pin "2") (pinfunction "2_2") (pintype "passive"))
      (node (ref "Q010") (pin "2") (pinfunction "B_2") (pintype "passive"))
      (node (ref "R053") (pin "2") (pinfunction "2_2") (pintype "passive"))
    )
    (net (code "70") (name "Net-(Q010-E)") (class "Default")
      (node (ref "Q010") (pin "3") (pinfunction "E_3") (pintype "passive"))
      (node (ref "R046") (pin "1") (pinfunction "1_1") (pintype "passive"))
      (node (ref "R054") (pin "2") (pinfunction "2_2") (pintype "passive"))
    )
    (net (code "71") (name "Net-(Q011-G)") (class "Default")
      (node (ref "C042") (pin "1") (pinfunction "1_1") (pintype "passive"))
      (node (ref "Q011") (pin "1") (pinfunction "G_1") (pintype "passive"))
      (node (ref "R058") (pin "2") (pinfunction "2_2") (pintype "passive"))
    )
    (net (code "72") (name "Net-(Q011-S)") (class "Default")
      (node (ref "C039") (pin "+") (pinfunction "+_+") (pintype "passive"))
      (node (ref "Q011") (pin "2") (pinfunction "S_2") (pintype "passive"))
      (node (ref "R055") (pin "1") (pinfunction "1_1") (pintype "passive"))
      (node (ref "R060") (pin "2") (pinfunction "2_2") (pintype "passive"))
    )
    (net (code "73") (name "Net-(R010-Pad2)") (class "Default")
      (node (ref "R010") (pin "2") (pinfunction "2_2") (pintype "passive"))
      (node (ref "ZD001") (pin "C") (pinfunction "C_C") (pintype "passive"))
    )
    (net (code "74") (name "Net-(R048-Pad1)") (class "Default")
      (node (ref "R048") (pin "1") (pinfunction "1_1") (pintype "passive"))
      (node (ref "VR02A") (pin "3") (pinfunction "3_3") (pintype "passive"))
    )
    (net (code "75") (name "Net-(R049-Pad1)") (class "Default")
      (node (ref "R049") (pin "1") (pinfunction "1_1") (pintype "passive"))
      (node (ref "VR02B") (pin "3") (pinfunction "3_3") (pintype "passive"))
    )
    (net (code "76") (name "Net-(R050-Pad1)") (class "Default")
      (node (ref "R050") (pin "1") (pinfunction "1_1") (pintype "passive"))
      (node (ref "VR02B") (pin "1") (pinfunction "1_1") (pintype "passive"))
    )
    (net (code "77") (name "Net-(R061-Pad2)") (class "Default")
      (node (ref "R061") (pin "2") (pinfunction "2_2") (pintype "passive"))
      (node (ref "VR03B") (pin "2") (pinfunction "2_2") (pintype "passive"))
    )
    (net (code "78") (name "Net-(R062-Pad2)") (class "Default")
      (node (ref "R062") (pin "2") (pinfunction "2_2") (pintype "passive"))
      (node (ref "VR02A ") (pin "3") (pinfunction "3_3") (pintype "passive"))
    )
    (net (code "79") (name "Net-(SW1-P)") (class "Default")
      (node (ref "R018") (pin "2") (pinfunction "2_2") (pintype "passive"))
      (node (ref "SW1") (pin "1") (pinfunction "P_1") (pintype "passive"))
    )
    (net (code "80") (name "OUT") (class "Default")
      (node (ref "R001") (pin "2") (pinfunction "2_2") (pintype "passive"))
    )
    (net (code "81") (name "VA") (class "Default")
      (node (ref "R016") (pin "2") (pinfunction "2_2") (pintype "passive"))
      (node (ref "R017") (pin "2") (pinfunction "2_2") (pintype "passive"))
      (node (ref "R023") (pin "2") (pinfunction "2_2") (pintype "passive"))
    )
    (net (code "82") (name "VB") (class "Default")
      (node (ref "C019") (pin "+") (pinfunction "+_+") (pintype "passive"))
      (node (ref "C031") (pin "2") (pinfunction "2_2") (pintype "passive"))
      (node (ref "C040") (pin "+") (pinfunction "+_+") (pintype "passive"))
      (node (ref "IC4") (pin "3") (pinfunction "+IN_3") (pintype "input"))
      (node (ref "R004") (pin "1") (pinfunction "1_1") (pintype "passive"))
      (node (ref "R005") (pin "1") (pinfunction "1_1") (pintype "passive"))
      (node (ref "R006") (pin "1") (pinfunction "1_1") (pintype "passive"))
      (node (ref "R007") (pin "1") (pinfunction "1_1") (pintype "passive"))
      (node (ref "R013") (pin "1") (pinfunction "1_1") (pintype "passive"))
      (node (ref "R025") (pin "1") (pinfunction "1_1") (pintype "passive"))
      (node (ref "R029") (pin "1") (pinfunction "1_1") (pintype "passive"))
      (node (ref "R036") (pin "1") (pinfunction "1_1") (pintype "passive"))
      (node (ref "R039") (pin "1") (pinfunction "1_1") (pintype "passive"))
      (node (ref "R040") (pin "1") (pinfunction "1_1") (pintype "passive"))
      (node (ref "R042") (pin "1") (pinfunction "1_1") (pintype "passive"))
      (node (ref "R043") (pin "1") (pinfunction "1_1") (pintype "passive"))
      (node (ref "R047") (pin "1") (pinfunction "1_1") (pintype "passive"))
      (node (ref "R052") (pin "1") (pinfunction "1_1") (pintype "passive"))
      (node (ref "R053") (pin "1") (pinfunction "1_1") (pintype "passive"))
      (node (ref "R056") (pin "1") (pinfunction "1_1") (pintype "passive"))
      (node (ref "R057") (pin "2") (pinfunction "2_2") (pintype "passive"))
      (node (ref "R058") (pin "1") (pinfunction "1_1") (pintype "passive"))
    )
  )
)
